# B131F.net
KiCad netlist of a schematic drawn in EAGLE
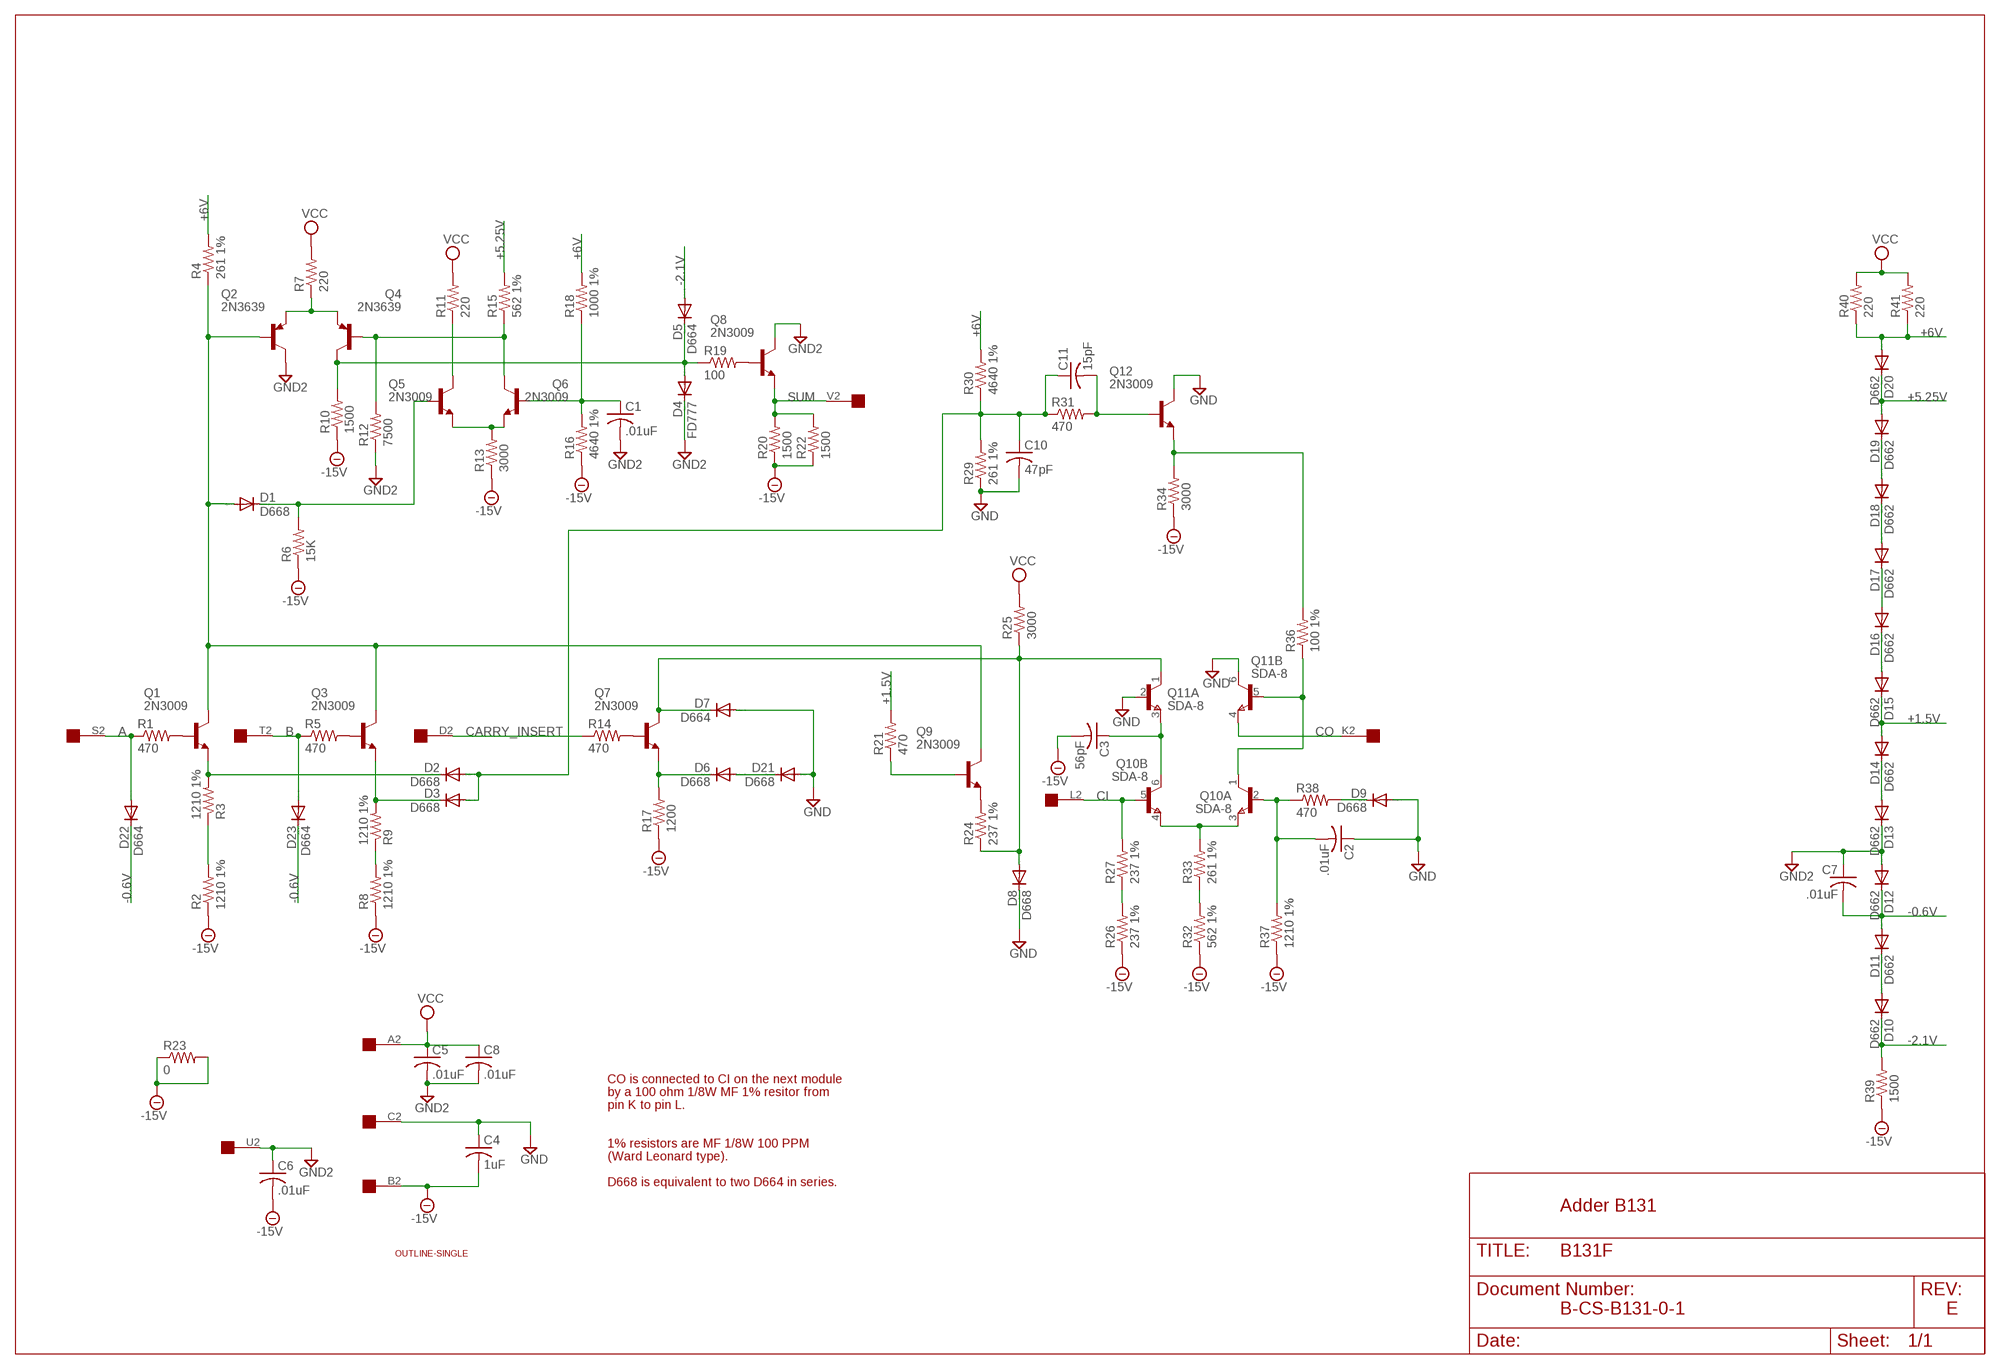
[diagram p0: schematic, sheet 1]

(export (version "E")
  (design (tool "Eeschema 10.0.6"))
  (components
    (comp (ref "C1")
      (value ".01uF")
      (footprint "eagle-import:C063-025X075")
      (libsource (lib "eagle-import") (part "C-US"))
    )
    (comp (ref "C2")
      (value ".01uF")
      (footprint "eagle-import:C063-025X075")
      (libsource (lib "eagle-import") (part "C-US"))
    )
    (comp (ref "C3")
      (value "56pF")
      (footprint "eagle-import:C063-025X075")
      (libsource (lib "eagle-import") (part "C-US"))
    )
    (comp (ref "C4")
      (value "1uF")
      (footprint "eagle-import:C102-043X133")
      (libsource (lib "eagle-import") (part "C-US102-043X133"))
    )
    (comp (ref "C5")
      (value ".01uF")
      (footprint "eagle-import:C063-025X075")
      (libsource (lib "eagle-import") (part "C-US"))
    )
    (comp (ref "C6")
      (value ".01uF")
      (footprint "eagle-import:C063-025X075")
      (libsource (lib "eagle-import") (part "C-US"))
    )
    (comp (ref "C7")
      (value ".01uF")
      (footprint "eagle-import:C063-025X075")
      (libsource (lib "eagle-import") (part "C-US"))
    )
    (comp (ref "C8")
      (value ".01uF")
      (footprint "eagle-import:C063-025X075")
      (libsource (lib "eagle-import") (part "C-US"))
    )
    (comp (ref "C10")
      (value "47pF")
      (footprint "eagle-import:C063-025X075")
      (libsource (lib "eagle-import") (part "C-US"))
    )
    (comp (ref "C11")
      (value "15pF")
      (footprint "eagle-import:C063-025X075")
      (libsource (lib "eagle-import") (part "C-US"))
    )
    (comp (ref "D1")
      (value "D668")
      (footprint "eagle-import:DO35-10")
      (libsource (lib "eagle-import") (part "DIODE-DO35-10"))
    )
    (comp (ref "D2")
      (value "D668")
      (footprint "eagle-import:DO35-10")
      (libsource (lib "eagle-import") (part "DIODE-DO35-10"))
    )
    (comp (ref "D3")
      (value "D668")
      (footprint "eagle-import:DO35-10")
      (libsource (lib "eagle-import") (part "DIODE-DO35-10"))
    )
    (comp (ref "D4")
      (value "FD777")
      (footprint "eagle-import:DO35-10")
      (libsource (lib "eagle-import") (part "DIODE-DO35-10"))
    )
    (comp (ref "D5")
      (value "D664")
      (footprint "eagle-import:DO35-10")
      (libsource (lib "eagle-import") (part "DIODE-DO35-10"))
    )
    (comp (ref "D6")
      (value "D668")
      (footprint "eagle-import:DO35-10")
      (libsource (lib "eagle-import") (part "DIODE-DO35-10"))
    )
    (comp (ref "D7")
      (value "D664")
      (footprint "eagle-import:DO35-10")
      (libsource (lib "eagle-import") (part "DIODE-DO35-10"))
    )
    (comp (ref "D8")
      (value "D668")
      (footprint "eagle-import:DO35-10")
      (libsource (lib "eagle-import") (part "DIODE-DO35-10"))
    )
    (comp (ref "D9")
      (value "D668")
      (footprint "eagle-import:DO35-10")
      (libsource (lib "eagle-import") (part "DIODE-DO35-10"))
    )
    (comp (ref "D10")
      (value "D662")
      (footprint "eagle-import:DO35-10")
      (libsource (lib "eagle-import") (part "DIODE-DO35-10"))
    )
    (comp (ref "D11")
      (value "D662")
      (footprint "eagle-import:DO35-10")
      (libsource (lib "eagle-import") (part "DIODE-DO35-10"))
    )
    (comp (ref "D12")
      (value "D662")
      (footprint "eagle-import:DO35-10")
      (libsource (lib "eagle-import") (part "DIODE-DO35-10"))
    )
    (comp (ref "D13")
      (value "D662")
      (footprint "eagle-import:DO35-10")
      (libsource (lib "eagle-import") (part "DIODE-DO35-10"))
    )
    (comp (ref "D14")
      (value "D662")
      (footprint "eagle-import:DO35-10")
      (libsource (lib "eagle-import") (part "DIODE-DO35-10"))
    )
    (comp (ref "D15")
      (value "D662")
      (footprint "eagle-import:DO35-10")
      (libsource (lib "eagle-import") (part "DIODE-DO35-10"))
    )
    (comp (ref "D16")
      (value "D662")
      (footprint "eagle-import:DO35-10")
      (libsource (lib "eagle-import") (part "DIODE-DO35-10"))
    )
    (comp (ref "D17")
      (value "D662")
      (footprint "eagle-import:DO35-10")
      (libsource (lib "eagle-import") (part "DIODE-DO35-10"))
    )
    (comp (ref "D18")
      (value "D662")
      (footprint "eagle-import:DO35-10")
      (libsource (lib "eagle-import") (part "DIODE-DO35-10"))
    )
    (comp (ref "D19")
      (value "D662")
      (footprint "eagle-import:DO35-10")
      (libsource (lib "eagle-import") (part "DIODE-DO35-10"))
    )
    (comp (ref "D20")
      (value "D662")
      (footprint "eagle-import:DO35-10")
      (libsource (lib "eagle-import") (part "DIODE-DO35-10"))
    )
    (comp (ref "D21")
      (value "D668")
      (footprint "eagle-import:DO35-10")
      (libsource (lib "eagle-import") (part "DIODE-DO35-10"))
    )
    (comp (ref "D22")
      (value "D664")
      (footprint "eagle-import:DO35-10")
      (libsource (lib "eagle-import") (part "DIODE-DO35-10"))
    )
    (comp (ref "D23")
      (value "D664")
      (footprint "eagle-import:DO35-10")
      (libsource (lib "eagle-import") (part "DIODE-DO35-10"))
    )
    (comp (ref "Q1")
      (value "2N3009")
      (footprint "eagle-import:TO5")
      (libsource (lib "eagle-import") (part "-NPN-TO5"))
    )
    (comp (ref "Q2")
      (value "2N3639")
      (footprint "eagle-import:TO5")
      (libsource (lib "eagle-import") (part "-PNP-TO5"))
    )
    (comp (ref "Q3")
      (value "2N3009")
      (footprint "eagle-import:TO5")
      (libsource (lib "eagle-import") (part "-NPN-TO5"))
    )
    (comp (ref "Q4")
      (value "2N3639")
      (footprint "eagle-import:TO5")
      (libsource (lib "eagle-import") (part "-PNP-TO5"))
    )
    (comp (ref "Q5")
      (value "2N3009")
      (footprint "eagle-import:TO5")
      (libsource (lib "eagle-import") (part "-NPN-TO5"))
    )
    (comp (ref "Q6")
      (value "2N3009")
      (footprint "eagle-import:TO5")
      (libsource (lib "eagle-import") (part "-NPN-TO5"))
    )
    (comp (ref "Q7")
      (value "2N3009")
      (footprint "eagle-import:TO5")
      (libsource (lib "eagle-import") (part "-NPN-TO5"))
    )
    (comp (ref "Q8")
      (value "2N3009")
      (footprint "eagle-import:TO5")
      (libsource (lib "eagle-import") (part "-NPN-TO5"))
    )
    (comp (ref "Q9")
      (value "2N3009")
      (footprint "eagle-import:TO5")
      (libsource (lib "eagle-import") (part "-NPN-TO5"))
    )
    (comp (ref "Q10")
      (value "SDA-8")
      (footprint "eagle-import:TO78")
      (libsource (lib "eagle-import") (part "MAT-02H"))
    )
    (comp (ref "Q11")
      (value "SDA-8")
      (footprint "eagle-import:TO78")
      (libsource (lib "eagle-import") (part "MAT-02H"))
    )
    (comp (ref "Q12")
      (value "2N3009")
      (footprint "eagle-import:TO5")
      (libsource (lib "eagle-import") (part "-NPN-TO5"))
    )
    (comp (ref "R1")
      (value "470")
      (footprint "eagle-import:0207_10")
      (libsource (lib "eagle-import") (part "R-US_0207/10"))
    )
    (comp (ref "R2")
      (value "1210 1%")
      (footprint "eagle-import:0207_15")
      (libsource (lib "eagle-import") (part "R-US_0207/15"))
    )
    (comp (ref "R3")
      (value "1210 1%")
      (footprint "eagle-import:0207_15")
      (libsource (lib "eagle-import") (part "R-US_0207/15"))
    )
    (comp (ref "R4")
      (value "261 1%")
      (footprint "eagle-import:0207_15")
      (libsource (lib "eagle-import") (part "R-US_0207/15"))
    )
    (comp (ref "R5")
      (value "470")
      (footprint "eagle-import:0207_10")
      (libsource (lib "eagle-import") (part "R-US_0207/10"))
    )
    (comp (ref "R6")
      (value "15K")
      (footprint "eagle-import:0207_10")
      (libsource (lib "eagle-import") (part "R-US_0207/10"))
    )
    (comp (ref "R7")
      (value "220")
      (footprint "eagle-import:0207_10")
      (libsource (lib "eagle-import") (part "R-US_0207/10"))
    )
    (comp (ref "R8")
      (value "1210 1%")
      (footprint "eagle-import:0207_15")
      (libsource (lib "eagle-import") (part "R-US_0207/15"))
    )
    (comp (ref "R9")
      (value "1210 1%")
      (footprint "eagle-import:0207_15")
      (libsource (lib "eagle-import") (part "R-US_0207/15"))
    )
    (comp (ref "R10")
      (value "1500")
      (footprint "eagle-import:0207_10")
      (libsource (lib "eagle-import") (part "R-US_0207/10"))
    )
    (comp (ref "R11")
      (value "220")
      (footprint "eagle-import:0207_10")
      (libsource (lib "eagle-import") (part "R-US_0207/10"))
    )
    (comp (ref "R12")
      (value "7500")
      (footprint "eagle-import:0207_10")
      (libsource (lib "eagle-import") (part "R-US_0207/10"))
    )
    (comp (ref "R13")
      (value "3000")
      (footprint "eagle-import:0207_10")
      (libsource (lib "eagle-import") (part "R-US_0207/10"))
    )
    (comp (ref "R14")
      (value "470")
      (footprint "eagle-import:0207_10")
      (libsource (lib "eagle-import") (part "R-US_0207/10"))
    )
    (comp (ref "R15")
      (value "562 1%")
      (footprint "eagle-import:0207_15")
      (libsource (lib "eagle-import") (part "R-US_0207/15"))
    )
    (comp (ref "R16")
      (value "4640 1%")
      (footprint "eagle-import:0207_15")
      (libsource (lib "eagle-import") (part "R-US_0207/15"))
    )
    (comp (ref "R17")
      (value "1200")
      (footprint "eagle-import:0207_10")
      (libsource (lib "eagle-import") (part "R-US_0207/10"))
    )
    (comp (ref "R18")
      (value "1000 1%")
      (footprint "eagle-import:0207_15")
      (libsource (lib "eagle-import") (part "R-US_0207/15"))
    )
    (comp (ref "R19")
      (value "100")
      (footprint "eagle-import:0207_10")
      (libsource (lib "eagle-import") (part "R-US_0207/10"))
    )
    (comp (ref "R20")
      (value "1500")
      (footprint "eagle-import:0207_10")
      (libsource (lib "eagle-import") (part "R-US_0207/10"))
    )
    (comp (ref "R21")
      (value "470")
      (footprint "eagle-import:0207_10")
      (libsource (lib "eagle-import") (part "R-US_0207/10"))
    )
    (comp (ref "R22")
      (value "1500")
      (footprint "eagle-import:0207_10")
      (libsource (lib "eagle-import") (part "R-US_0207/10"))
    )
    (comp (ref "R23")
      (value "0")
      (footprint "eagle-import:0207_10")
      (libsource (lib "eagle-import") (part "R-US_0207/10"))
    )
    (comp (ref "R24")
      (value "237 1%")
      (footprint "eagle-import:0207_15")
      (libsource (lib "eagle-import") (part "R-US_0207/15"))
    )
    (comp (ref "R25")
      (value "3000")
      (footprint "eagle-import:0207_10")
      (libsource (lib "eagle-import") (part "R-US_0207/10"))
    )
    (comp (ref "R26")
      (value "237 1%")
      (footprint "eagle-import:0207_15")
      (libsource (lib "eagle-import") (part "R-US_0207/15"))
    )
    (comp (ref "R27")
      (value "237 1%")
      (footprint "eagle-import:0207_15")
      (libsource (lib "eagle-import") (part "R-US_0207/15"))
    )
    (comp (ref "R29")
      (value "261 1%")
      (footprint "eagle-import:0207_15")
      (libsource (lib "eagle-import") (part "R-US_0207/15"))
    )
    (comp (ref "R30")
      (value "4640 1%")
      (footprint "eagle-import:0207_15")
      (libsource (lib "eagle-import") (part "R-US_0207/15"))
    )
    (comp (ref "R31")
      (value "470")
      (footprint "eagle-import:0207_10")
      (libsource (lib "eagle-import") (part "R-US_0207/10"))
    )
    (comp (ref "R32")
      (value "562 1%")
      (footprint "eagle-import:0207_15")
      (libsource (lib "eagle-import") (part "R-US_0207/15"))
    )
    (comp (ref "R33")
      (value "261 1%")
      (footprint "eagle-import:0207_15")
      (libsource (lib "eagle-import") (part "R-US_0207/15"))
    )
    (comp (ref "R34")
      (value "3000")
      (footprint "eagle-import:0207_10")
      (libsource (lib "eagle-import") (part "R-US_0207/10"))
    )
    (comp (ref "R36")
      (value "100 1%")
      (footprint "eagle-import:0207_15")
      (libsource (lib "eagle-import") (part "R-US_0207/15"))
    )
    (comp (ref "R37")
      (value "1210 1%")
      (footprint "eagle-import:0207_15")
      (libsource (lib "eagle-import") (part "R-US_0207/15"))
    )
    (comp (ref "R38")
      (value "470")
      (footprint "eagle-import:0207_10")
      (libsource (lib "eagle-import") (part "R-US_0207/10"))
    )
    (comp (ref "R39")
      (value "1500")
      (footprint "eagle-import:0207_10")
      (libsource (lib "eagle-import") (part "R-US_0207/10"))
    )
    (comp (ref "R40")
      (value "220")
      (footprint "eagle-import:0207_10")
      (libsource (lib "eagle-import") (part "R-US_0207/10"))
    )
    (comp (ref "R41")
      (value "220")
      (footprint "eagle-import:0207_10")
      (libsource (lib "eagle-import") (part "R-US_0207/10"))
    )
    (comp (ref "U$1")
      (value "OUTLINE-SINGLE")
      (footprint "eagle-import:SINGLE")
      (libsource (lib "eagle-import") (part "OUTLINE-SINGLE"))
    )
    (comp (ref "U$2")
      (value "EDGE-1")
      (footprint "eagle-import:EDGE-CON1")
      (libsource (lib "eagle-import") (part "EDGE-1"))
    )
  )
  (nets
    (net (code "1") (name "-15V") (class "Default")
      (node (ref "C3") (pin "2") (pinfunction "2_2") (pintype "passive"))
      (node (ref "C4") (pin "2") (pinfunction "2_2") (pintype "passive"))
      (node (ref "C6") (pin "2") (pinfunction "2_2") (pintype "passive"))
      (node (ref "R10") (pin "1") (pinfunction "1_1") (pintype "passive"))
      (node (ref "R13") (pin "1") (pinfunction "1_1") (pintype "passive"))
      (node (ref "R16") (pin "1") (pinfunction "1_1") (pintype "passive"))
      (node (ref "R17") (pin "1") (pinfunction "1_1") (pintype "passive"))
      (node (ref "R2") (pin "1") (pinfunction "1_1") (pintype "passive"))
      (node (ref "R20") (pin "1") (pinfunction "1_1") (pintype "passive"))
      (node (ref "R22") (pin "1") (pinfunction "1_1") (pintype "passive"))
      (node (ref "R23") (pin "1") (pinfunction "1_1") (pintype "passive"))
      (node (ref "R23") (pin "2") (pinfunction "2_2") (pintype "passive"))
      (node (ref "R26") (pin "1") (pinfunction "1_1") (pintype "passive"))
      (node (ref "R32") (pin "1") (pinfunction "1_1") (pintype "passive"))
      (node (ref "R34") (pin "1") (pinfunction "1_1") (pintype "passive"))
      (node (ref "R37") (pin "1") (pinfunction "1_1") (pintype "passive"))
      (node (ref "R39") (pin "1") (pinfunction "1_1") (pintype "passive"))
      (node (ref "R6") (pin "1") (pinfunction "1_1") (pintype "passive"))
      (node (ref "R8") (pin "1") (pinfunction "1_1") (pintype "passive"))
      (node (ref "U$2") (pin "B2") (pinfunction "1_B2") (pintype "bidirectional"))
    )
    (net (code "2") (name "/+1.5V") (class "Default")
      (node (ref "D14") (pin "A") (pinfunction "A_A") (pintype "passive"))
      (node (ref "D15") (pin "C") (pinfunction "C_C") (pintype "passive"))
      (node (ref "R21") (pin "2") (pinfunction "2_2") (pintype "passive"))
    )
    (net (code "3") (name "/+5.25V") (class "Default")
      (node (ref "D19") (pin "A") (pinfunction "A_A") (pintype "passive"))
      (node (ref "D20") (pin "C") (pinfunction "C_C") (pintype "passive"))
      (node (ref "R15") (pin "2") (pinfunction "2_2") (pintype "passive"))
    )
    (net (code "4") (name "/+6V") (class "Default")
      (node (ref "D20") (pin "A") (pinfunction "A_A") (pintype "passive"))
      (node (ref "R18") (pin "2") (pinfunction "2_2") (pintype "passive"))
      (node (ref "R30") (pin "2") (pinfunction "2_2") (pintype "passive"))
      (node (ref "R4") (pin "2") (pinfunction "2_2") (pintype "passive"))
      (node (ref "R40") (pin "1") (pinfunction "1_1") (pintype "passive"))
      (node (ref "R41") (pin "1") (pinfunction "1_1") (pintype "passive"))
    )
    (net (code "5") (name "/-0.6V") (class "Default")
      (node (ref "C7") (pin "2") (pinfunction "2_2") (pintype "passive"))
      (node (ref "D11") (pin "A") (pinfunction "A_A") (pintype "passive"))
      (node (ref "D12") (pin "C") (pinfunction "C_C") (pintype "passive"))
      (node (ref "D22") (pin "C") (pinfunction "C_C") (pintype "passive"))
      (node (ref "D23") (pin "C") (pinfunction "C_C") (pintype "passive"))
    )
    (net (code "6") (name "/-2.1V") (class "Default")
      (node (ref "D10") (pin "C") (pinfunction "C_C") (pintype "passive"))
      (node (ref "D5") (pin "A") (pinfunction "A_A") (pintype "passive"))
      (node (ref "R39") (pin "2") (pinfunction "2_2") (pintype "passive"))
    )
    (net (code "7") (name "/A") (class "Default")
      (node (ref "D22") (pin "A") (pinfunction "A_A") (pintype "passive"))
      (node (ref "R1") (pin "1") (pinfunction "1_1") (pintype "passive"))
      (node (ref "U$2") (pin "S2") (pinfunction "1_S2") (pintype "bidirectional"))
    )
    (net (code "8") (name "/B") (class "Default")
      (node (ref "D23") (pin "A") (pinfunction "A_A") (pintype "passive"))
      (node (ref "R5") (pin "1") (pinfunction "1_1") (pintype "passive"))
      (node (ref "U$2") (pin "T2") (pinfunction "1_T2") (pintype "bidirectional"))
    )
    (net (code "9") (name "/CARRY_INSERT") (class "Default")
      (node (ref "R14") (pin "1") (pinfunction "1_1") (pintype "passive"))
      (node (ref "U$2") (pin "D2") (pinfunction "1_D2") (pintype "bidirectional"))
    )
    (net (code "10") (name "/CI") (class "Default")
      (node (ref "Q10") (pin "5") (pinfunction "B_5") (pintype "passive"))
      (node (ref "R27") (pin "2") (pinfunction "2_2") (pintype "passive"))
      (node (ref "U$2") (pin "L2") (pinfunction "1_L2") (pintype "bidirectional"))
    )
    (net (code "11") (name "/CO") (class "Default")
      (node (ref "Q11") (pin "4") (pinfunction "E_4") (pintype "passive"))
      (node (ref "U$2") (pin "K2") (pinfunction "1_K2") (pintype "bidirectional"))
    )
    (net (code "12") (name "/SUM") (class "Default")
      (node (ref "Q8") (pin "1") (pinfunction "E_1") (pintype "passive"))
      (node (ref "R20") (pin "2") (pinfunction "2_2") (pintype "passive"))
      (node (ref "R22") (pin "2") (pinfunction "2_2") (pintype "passive"))
      (node (ref "U$2") (pin "V2") (pinfunction "1_V2") (pintype "bidirectional"))
    )
    (net (code "13") (name "GND") (class "Default")
      (node (ref "C10") (pin "2") (pinfunction "2_2") (pintype "passive"))
      (node (ref "C2") (pin "1") (pinfunction "1_1") (pintype "passive"))
      (node (ref "C4") (pin "1") (pinfunction "1_1") (pintype "passive"))
      (node (ref "D21") (pin "A") (pinfunction "A_A") (pintype "passive"))
      (node (ref "D7") (pin "A") (pinfunction "A_A") (pintype "passive"))
      (node (ref "D8") (pin "C") (pinfunction "C_C") (pintype "passive"))
      (node (ref "D9") (pin "A") (pinfunction "A_A") (pintype "passive"))
      (node (ref "Q11") (pin "2") (pinfunction "B_2") (pintype "passive"))
      (node (ref "Q11") (pin "6") (pinfunction "C_6") (pintype "passive"))
      (node (ref "Q12") (pin "3") (pinfunction "C_3") (pintype "passive"))
      (node (ref "R29") (pin "1") (pinfunction "1_1") (pintype "passive"))
      (node (ref "U$2") (pin "C2") (pinfunction "1_C2") (pintype "bidirectional"))
    )
    (net (code "14") (name "GND2") (class "Default")
      (node (ref "C1") (pin "2") (pinfunction "2_2") (pintype "passive"))
      (node (ref "C5") (pin "2") (pinfunction "2_2") (pintype "passive"))
      (node (ref "C6") (pin "1") (pinfunction "1_1") (pintype "passive"))
      (node (ref "C7") (pin "1") (pinfunction "1_1") (pintype "passive"))
      (node (ref "C8") (pin "2") (pinfunction "2_2") (pintype "passive"))
      (node (ref "D12") (pin "A") (pinfunction "A_A") (pintype "passive"))
      (node (ref "D13") (pin "C") (pinfunction "C_C") (pintype "passive"))
      (node (ref "D4") (pin "C") (pinfunction "C_C") (pintype "passive"))
      (node (ref "Q2") (pin "3") (pinfunction "C_3") (pintype "passive"))
      (node (ref "Q8") (pin "3") (pinfunction "C_3") (pintype "passive"))
      (node (ref "R12") (pin "1") (pinfunction "1_1") (pintype "passive"))
      (node (ref "U$2") (pin "U2") (pinfunction "1_U2") (pintype "bidirectional"))
    )
    (net (code "15") (name "Net-(C10-Pad1)") (class "Default")
      (node (ref "C10") (pin "1") (pinfunction "1_1") (pintype "passive"))
      (node (ref "C11") (pin "1") (pinfunction "1_1") (pintype "passive"))
      (node (ref "D2") (pin "A") (pinfunction "A_A") (pintype "passive"))
      (node (ref "D3") (pin "A") (pinfunction "A_A") (pintype "passive"))
      (node (ref "R29") (pin "2") (pinfunction "2_2") (pintype "passive"))
      (node (ref "R30") (pin "1") (pinfunction "1_1") (pintype "passive"))
      (node (ref "R31") (pin "1") (pinfunction "1_1") (pintype "passive"))
    )
    (net (code "16") (name "Net-(D9-PadC)") (class "Default")
      (node (ref "D9") (pin "C") (pinfunction "C_C") (pintype "passive"))
      (node (ref "R38") (pin "2") (pinfunction "2_2") (pintype "passive"))
    )
    (net (code "17") (name "Net-(D10-PadA)") (class "Default")
      (node (ref "D10") (pin "A") (pinfunction "A_A") (pintype "passive"))
      (node (ref "D11") (pin "C") (pinfunction "C_C") (pintype "passive"))
    )
    (net (code "18") (name "Net-(D13-PadA)") (class "Default")
      (node (ref "D13") (pin "A") (pinfunction "A_A") (pintype "passive"))
      (node (ref "D14") (pin "C") (pinfunction "C_C") (pintype "passive"))
    )
    (net (code "19") (name "Net-(D15-PadA)") (class "Default")
      (node (ref "D15") (pin "A") (pinfunction "A_A") (pintype "passive"))
      (node (ref "D16") (pin "C") (pinfunction "C_C") (pintype "passive"))
    )
    (net (code "20") (name "Net-(D16-PadA)") (class "Default")
      (node (ref "D16") (pin "A") (pinfunction "A_A") (pintype "passive"))
      (node (ref "D17") (pin "C") (pinfunction "C_C") (pintype "passive"))
    )
    (net (code "21") (name "Net-(D17-PadA)") (class "Default")
      (node (ref "D17") (pin "A") (pinfunction "A_A") (pintype "passive"))
      (node (ref "D18") (pin "C") (pinfunction "C_C") (pintype "passive"))
    )
    (net (code "22") (name "Net-(D18-PadA)") (class "Default")
      (node (ref "D18") (pin "A") (pinfunction "A_A") (pintype "passive"))
      (node (ref "D19") (pin "C") (pinfunction "C_C") (pintype "passive"))
    )
    (net (code "23") (name "Net-(D21-PadC)") (class "Default")
      (node (ref "D21") (pin "C") (pinfunction "C_C") (pintype "passive"))
      (node (ref "D6") (pin "A") (pinfunction "A_A") (pintype "passive"))
    )
    (net (code "24") (name "Net-(Q1-B)") (class "Default")
      (node (ref "Q1") (pin "2") (pinfunction "B_2") (pintype "passive"))
      (node (ref "R1") (pin "2") (pinfunction "2_2") (pintype "passive"))
    )
    (net (code "25") (name "Net-(Q1-C)") (class "Default")
      (node (ref "D1") (pin "A") (pinfunction "A_A") (pintype "passive"))
      (node (ref "Q1") (pin "3") (pinfunction "C_3") (pintype "passive"))
      (node (ref "Q2") (pin "2") (pinfunction "B_2") (pintype "passive"))
      (node (ref "Q3") (pin "3") (pinfunction "C_3") (pintype "passive"))
      (node (ref "Q9") (pin "3") (pinfunction "C_3") (pintype "passive"))
      (node (ref "R4") (pin "1") (pinfunction "1_1") (pintype "passive"))
    )
    (net (code "26") (name "Net-(Q1-E)") (class "Default")
      (node (ref "D2") (pin "C") (pinfunction "C_C") (pintype "passive"))
      (node (ref "Q1") (pin "1") (pinfunction "E_1") (pintype "passive"))
      (node (ref "R3") (pin "2") (pinfunction "2_2") (pintype "passive"))
    )
    (net (code "27") (name "Net-(Q2-E)") (class "Default")
      (node (ref "Q2") (pin "1") (pinfunction "E_1") (pintype "passive"))
      (node (ref "Q4") (pin "1") (pinfunction "E_1") (pintype "passive"))
      (node (ref "R7") (pin "1") (pinfunction "1_1") (pintype "passive"))
    )
    (net (code "28") (name "Net-(Q3-B)") (class "Default")
      (node (ref "Q3") (pin "2") (pinfunction "B_2") (pintype "passive"))
      (node (ref "R5") (pin "2") (pinfunction "2_2") (pintype "passive"))
    )
    (net (code "29") (name "Net-(Q3-E)") (class "Default")
      (node (ref "D3") (pin "C") (pinfunction "C_C") (pintype "passive"))
      (node (ref "Q3") (pin "1") (pinfunction "E_1") (pintype "passive"))
      (node (ref "R9") (pin "2") (pinfunction "2_2") (pintype "passive"))
    )
    (net (code "30") (name "Net-(Q4-B)") (class "Default")
      (node (ref "Q4") (pin "2") (pinfunction "B_2") (pintype "passive"))
      (node (ref "Q6") (pin "3") (pinfunction "C_3") (pintype "passive"))
      (node (ref "R12") (pin "2") (pinfunction "2_2") (pintype "passive"))
      (node (ref "R15") (pin "1") (pinfunction "1_1") (pintype "passive"))
    )
    (net (code "31") (name "Net-(Q4-C)") (class "Default")
      (node (ref "D4") (pin "A") (pinfunction "A_A") (pintype "passive"))
      (node (ref "D5") (pin "C") (pinfunction "C_C") (pintype "passive"))
      (node (ref "Q4") (pin "3") (pinfunction "C_3") (pintype "passive"))
      (node (ref "R10") (pin "2") (pinfunction "2_2") (pintype "passive"))
      (node (ref "R19") (pin "1") (pinfunction "1_1") (pintype "passive"))
    )
    (net (code "32") (name "Net-(Q5-B)") (class "Default")
      (node (ref "D1") (pin "C") (pinfunction "C_C") (pintype "passive"))
      (node (ref "Q5") (pin "2") (pinfunction "B_2") (pintype "passive"))
      (node (ref "R6") (pin "2") (pinfunction "2_2") (pintype "passive"))
    )
    (net (code "33") (name "Net-(Q5-C)") (class "Default")
      (node (ref "Q5") (pin "3") (pinfunction "C_3") (pintype "passive"))
      (node (ref "R11") (pin "1") (pinfunction "1_1") (pintype "passive"))
    )
    (net (code "34") (name "Net-(Q5-E)") (class "Default")
      (node (ref "Q5") (pin "1") (pinfunction "E_1") (pintype "passive"))
      (node (ref "Q6") (pin "1") (pinfunction "E_1") (pintype "passive"))
      (node (ref "R13") (pin "2") (pinfunction "2_2") (pintype "passive"))
    )
    (net (code "35") (name "Net-(Q6-B)") (class "Default")
      (node (ref "C1") (pin "1") (pinfunction "1_1") (pintype "passive"))
      (node (ref "Q6") (pin "2") (pinfunction "B_2") (pintype "passive"))
      (node (ref "R16") (pin "2") (pinfunction "2_2") (pintype "passive"))
      (node (ref "R18") (pin "1") (pinfunction "1_1") (pintype "passive"))
    )
    (net (code "36") (name "Net-(Q7-B)") (class "Default")
      (node (ref "Q7") (pin "2") (pinfunction "B_2") (pintype "passive"))
      (node (ref "R14") (pin "2") (pinfunction "2_2") (pintype "passive"))
    )
    (net (code "37") (name "Net-(Q7-E)") (class "Default")
      (node (ref "D6") (pin "C") (pinfunction "C_C") (pintype "passive"))
      (node (ref "Q7") (pin "1") (pinfunction "E_1") (pintype "passive"))
      (node (ref "R17") (pin "2") (pinfunction "2_2") (pintype "passive"))
    )
    (net (code "38") (name "Net-(Q8-B)") (class "Default")
      (node (ref "Q8") (pin "2") (pinfunction "B_2") (pintype "passive"))
      (node (ref "R19") (pin "2") (pinfunction "2_2") (pintype "passive"))
    )
    (net (code "39") (name "Net-(Q9-B)") (class "Default")
      (node (ref "Q9") (pin "2") (pinfunction "B_2") (pintype "passive"))
      (node (ref "R21") (pin "1") (pinfunction "1_1") (pintype "passive"))
    )
    (net (code "40") (name "Net-(Q9-E)") (class "Default")
      (node (ref "Q9") (pin "1") (pinfunction "E_1") (pintype "passive"))
      (node (ref "R24") (pin "2") (pinfunction "2_2") (pintype "passive"))
    )
    (net (code "41") (name "Net-(Q10A-B)") (class "Default")
      (node (ref "C2") (pin "2") (pinfunction "2_2") (pintype "passive"))
      (node (ref "Q10") (pin "2") (pinfunction "B_2") (pintype "passive"))
      (node (ref "R37") (pin "2") (pinfunction "2_2") (pintype "passive"))
      (node (ref "R38") (pin "1") (pinfunction "1_1") (pintype "passive"))
    )
    (net (code "42") (name "Net-(Q10A-C)") (class "Default")
      (node (ref "Q10") (pin "1") (pinfunction "C_1") (pintype "passive"))
      (node (ref "Q11") (pin "5") (pinfunction "B_5") (pintype "passive"))
      (node (ref "R36") (pin "1") (pinfunction "1_1") (pintype "passive"))
    )
    (net (code "43") (name "Net-(Q10A-E)") (class "Default")
      (node (ref "Q10") (pin "3") (pinfunction "E_3") (pintype "passive"))
      (node (ref "Q10") (pin "4") (pinfunction "E_4") (pintype "passive"))
      (node (ref "R33") (pin "2") (pinfunction "2_2") (pintype "passive"))
    )
    (net (code "44") (name "Net-(Q10B-C)") (class "Default")
      (node (ref "C3") (pin "1") (pinfunction "1_1") (pintype "passive"))
      (node (ref "Q10") (pin "6") (pinfunction "C_6") (pintype "passive"))
      (node (ref "Q11") (pin "3") (pinfunction "E_3") (pintype "passive"))
    )
    (net (code "45") (name "Net-(Q11A-C)") (class "Default")
      (node (ref "D7") (pin "C") (pinfunction "C_C") (pintype "passive"))
      (node (ref "D8") (pin "A") (pinfunction "A_A") (pintype "passive"))
      (node (ref "Q11") (pin "1") (pinfunction "C_1") (pintype "passive"))
      (node (ref "Q7") (pin "3") (pinfunction "C_3") (pintype "passive"))
      (node (ref "R24") (pin "1") (pinfunction "1_1") (pintype "passive"))
      (node (ref "R25") (pin "1") (pinfunction "1_1") (pintype "passive"))
    )
    (net (code "46") (name "Net-(Q12-B)") (class "Default")
      (node (ref "C11") (pin "2") (pinfunction "2_2") (pintype "passive"))
      (node (ref "Q12") (pin "2") (pinfunction "B_2") (pintype "passive"))
      (node (ref "R31") (pin "2") (pinfunction "2_2") (pintype "passive"))
    )
    (net (code "47") (name "Net-(Q12-E)") (class "Default")
      (node (ref "Q12") (pin "1") (pinfunction "E_1") (pintype "passive"))
      (node (ref "R34") (pin "2") (pinfunction "2_2") (pintype "passive"))
      (node (ref "R36") (pin "2") (pinfunction "2_2") (pintype "passive"))
    )
    (net (code "48") (name "Net-(R2-Pad2)") (class "Default")
      (node (ref "R2") (pin "2") (pinfunction "2_2") (pintype "passive"))
      (node (ref "R3") (pin "1") (pinfunction "1_1") (pintype "passive"))
    )
    (net (code "49") (name "Net-(R8-Pad2)") (class "Default")
      (node (ref "R8") (pin "2") (pinfunction "2_2") (pintype "passive"))
      (node (ref "R9") (pin "1") (pinfunction "1_1") (pintype "passive"))
    )
    (net (code "50") (name "Net-(R26-Pad2)") (class "Default")
      (node (ref "R26") (pin "2") (pinfunction "2_2") (pintype "passive"))
      (node (ref "R27") (pin "1") (pinfunction "1_1") (pintype "passive"))
    )
    (net (code "51") (name "Net-(R32-Pad2)") (class "Default")
      (node (ref "R32") (pin "2") (pinfunction "2_2") (pintype "passive"))
      (node (ref "R33") (pin "1") (pinfunction "1_1") (pintype "passive"))
    )
    (net (code "52") (name "VCC") (class "Default")
      (node (ref "C5") (pin "1") (pinfunction "1_1") (pintype "passive"))
      (node (ref "C8") (pin "1") (pinfunction "1_1") (pintype "passive"))
      (node (ref "R11") (pin "2") (pinfunction "2_2") (pintype "passive"))
      (node (ref "R25") (pin "2") (pinfunction "2_2") (pintype "passive"))
      (node (ref "R40") (pin "2") (pinfunction "2_2") (pintype "passive"))
      (node (ref "R41") (pin "2") (pinfunction "2_2") (pintype "passive"))
      (node (ref "R7") (pin "2") (pinfunction "2_2") (pintype "passive"))
      (node (ref "U$2") (pin "A2") (pinfunction "1_A2") (pintype "bidirectional"))
    )
  )
)
